# Wobblebot_Teensy_reroutPWR.net
KiCad netlist of a schematic drawn in EAGLE
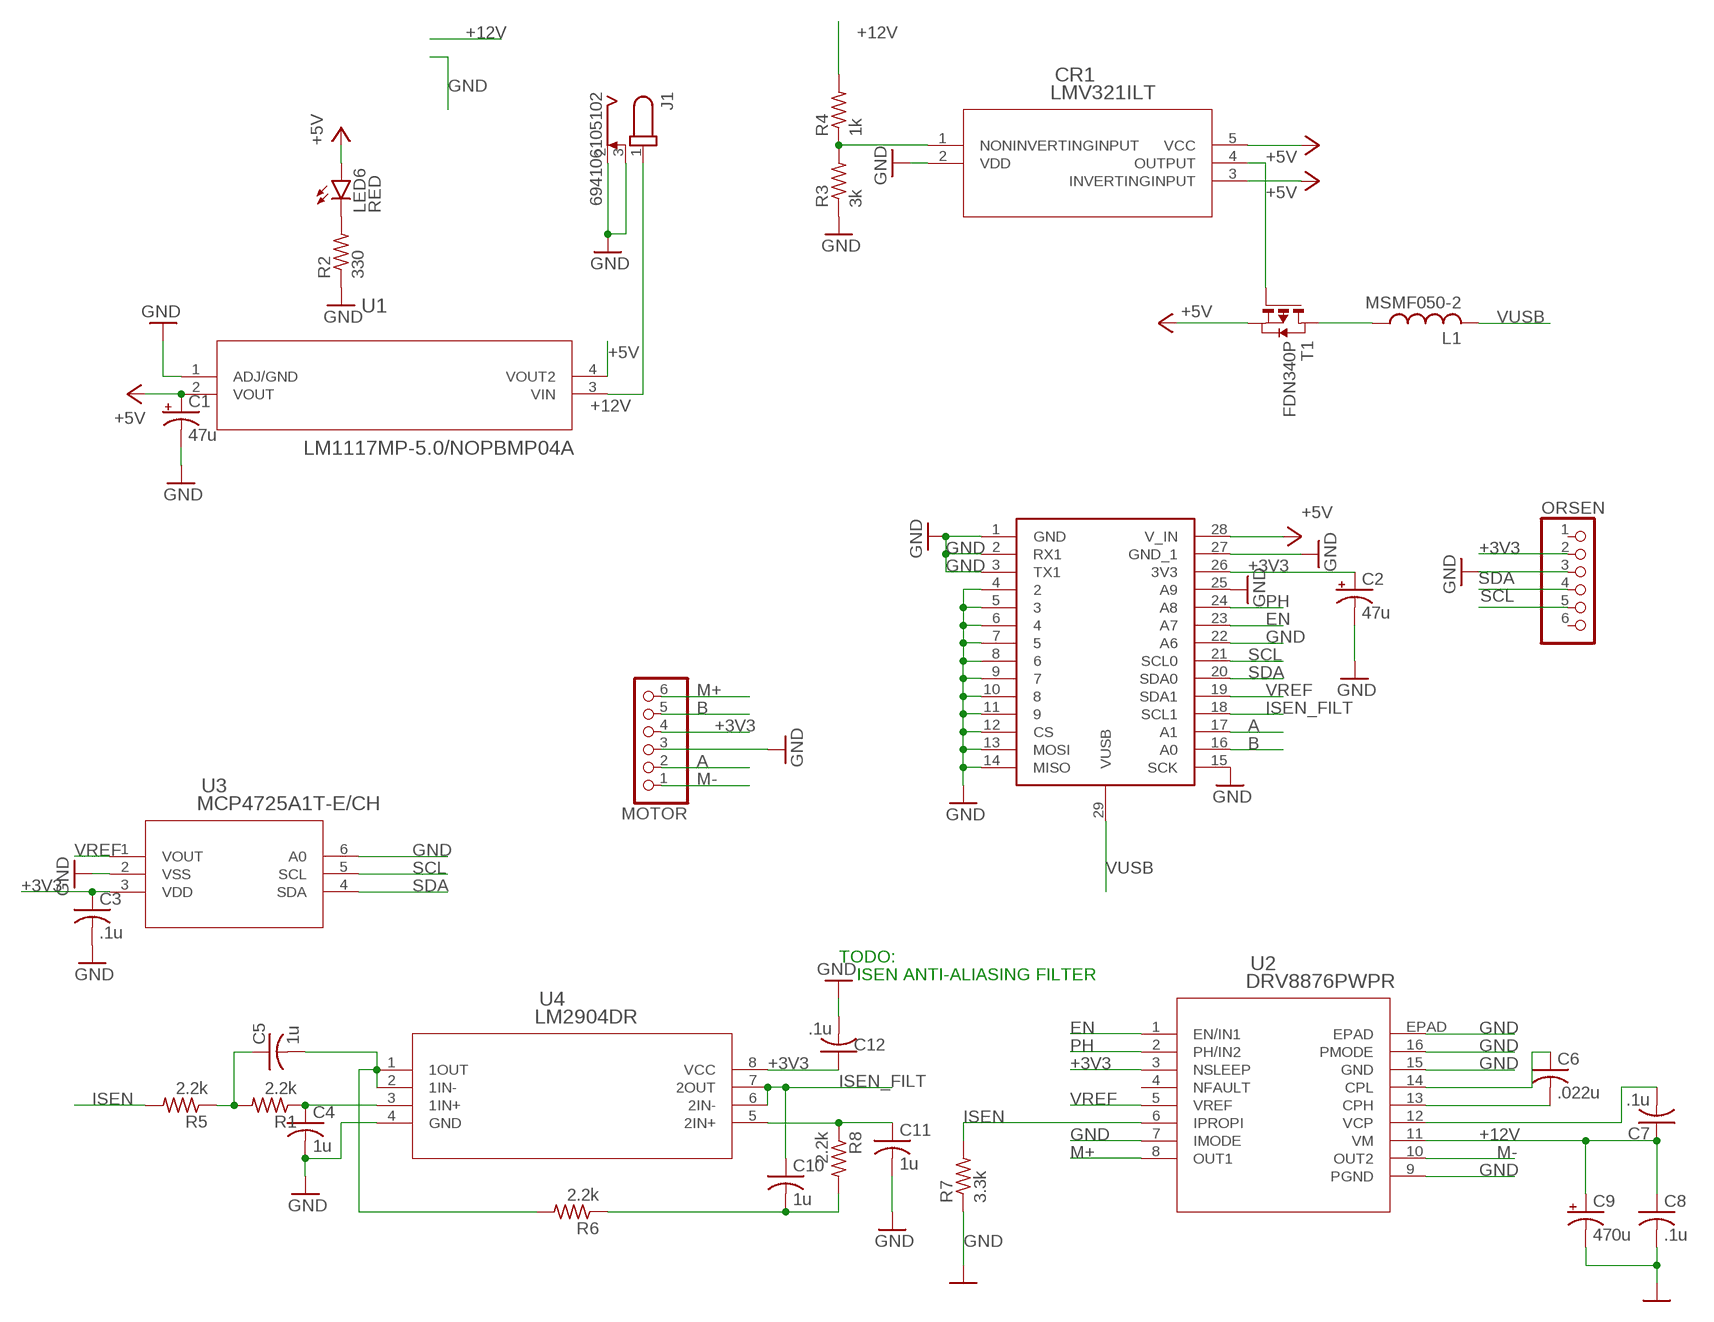
[diagram p0: schematic, sheet 1]

(export (version "E")
  (design (tool "Eeschema 10.0.6"))
  (components
    (comp (ref "C1")
      (value "47u")
      (footprint "eagle-import:153CLV-0605")
      (libsource (lib "eagle-import") (part "CPOL-US153CLV-0605"))
    )
    (comp (ref "C2")
      (value "47u")
      (footprint "eagle-import:153CLV-0605")
      (libsource (lib "eagle-import") (part "CPOL-US153CLV-0605"))
    )
    (comp (ref "C3")
      (value ".1u")
      (footprint "eagle-import:C0805")
      (libsource (lib "eagle-import") (part "C-USC0805"))
    )
    (comp (ref "C4")
      (value "1u")
      (footprint "eagle-import:C0805")
      (libsource (lib "eagle-import") (part "C-USC0805"))
    )
    (comp (ref "C5")
      (value "1u")
      (footprint "eagle-import:C0805")
      (libsource (lib "eagle-import") (part "C-USC0805"))
    )
    (comp (ref "C6")
      (value ".022u")
      (footprint "eagle-import:C0805")
      (libsource (lib "eagle-import") (part "C-USC0805"))
    )
    (comp (ref "C7")
      (value ".1u")
      (footprint "eagle-import:C0805")
      (libsource (lib "eagle-import") (part "C-USC0805"))
    )
    (comp (ref "C8")
      (value ".1u")
      (footprint "eagle-import:C0805")
      (libsource (lib "eagle-import") (part "C-USC0805"))
    )
    (comp (ref "C9")
      (value "470u")
      (footprint "eagle-import:E5-10,5")
      (libsource (lib "eagle-import") (part "CPOL-USE5-10.5"))
    )
    (comp (ref "C10")
      (value "1u")
      (footprint "eagle-import:C0805")
      (libsource (lib "eagle-import") (part "C-USC0805"))
    )
    (comp (ref "C11")
      (value "1u")
      (footprint "eagle-import:C0805")
      (libsource (lib "eagle-import") (part "C-USC0805"))
    )
    (comp (ref "C12")
      (value ".1u")
      (footprint "eagle-import:C0805")
      (libsource (lib "eagle-import") (part "C-USC0805"))
    )
    (comp (ref "CR1")
      (value "LMV321ILT")
      (footprint "eagle-import:SOT23-5")
      (libsource (lib "eagle-import") (part "LMV321ILT"))
    )
    (comp (ref "J1")
      (value "694106105102")
      (footprint "eagle-import:694106105102")
      (fields
        (field (name "DIGIKEY_PART_NUMBER") "732-5928-2-ND")
        (field (name "MANUFACTURER") "Wurth Electronics Inc.")
        (field (name "CREATED_BY") "PCBLayout.com")
      )
      (libsource (lib "eagle-import") (part "694106105102"))
    )
    (comp (ref "L1")
      (value "MSMF050-2")
      (footprint "eagle-import:L1812")
      (libsource (lib "eagle-import") (part "L-USL1812"))
    )
    (comp (ref "LED6")
      (value "RED")
      (footprint "eagle-import:CHIPLED_0805")
      (libsource (lib "eagle-import") (part "LEDCHIPLED_0805"))
    )
    (comp (ref "MOTOR")
      (value "PINHD-1X6")
      (footprint "eagle-import:1X06")
      (libsource (lib "eagle-import") (part "PINHD-1X6"))
    )
    (comp (ref "ORSEN")
      (value "PINHD-1X6")
      (footprint "eagle-import:1X06")
      (libsource (lib "eagle-import") (part "PINHD-1X6"))
    )
    (comp (ref "R1")
      (value "2.2k")
      (footprint "eagle-import:R0805")
      (libsource (lib "eagle-import") (part "R-US_R0805"))
    )
    (comp (ref "R2")
      (value "330")
      (footprint "eagle-import:R0805")
      (libsource (lib "eagle-import") (part "R-US_R0805"))
    )
    (comp (ref "R3")
      (value "3k")
      (footprint "eagle-import:R0805")
      (libsource (lib "eagle-import") (part "R-US_R0805"))
    )
    (comp (ref "R4")
      (value "1k")
      (footprint "eagle-import:R0805")
      (libsource (lib "eagle-import") (part "R-US_R0805"))
    )
    (comp (ref "R5")
      (value "2.2k")
      (footprint "eagle-import:R0805")
      (libsource (lib "eagle-import") (part "R-US_R0805"))
    )
    (comp (ref "R6")
      (value "2.2k")
      (footprint "eagle-import:R0805")
      (libsource (lib "eagle-import") (part "R-US_R0805"))
    )
    (comp (ref "R7")
      (value "3.3k")
      (footprint "eagle-import:R0805")
      (libsource (lib "eagle-import") (part "R-US_R0805"))
    )
    (comp (ref "R8")
      (value "2.2k")
      (footprint "eagle-import:R0805")
      (libsource (lib "eagle-import") (part "R-US_R0805"))
    )
    (comp (ref "T1")
      (value "FDN340P")
      (footprint "eagle-import:SOT-23")
      (libsource (lib "eagle-import") (part "PMOSSOT23"))
    )
    (comp (ref "U$1")
      (value "TEENSY4.0TEENSY4.0")
      (footprint "eagle-import:DIP1524W53P254L3810H508Q28B")
      (libsource (lib "eagle-import") (part "TEENSY4.0TEENSY4.0"))
    )
    (comp (ref "U1")
      (value "LM1117MP-5.0/NOPBMP04A")
      (footprint "eagle-import:MP04A")
      (fields (field (name "MANUFACTURER_PART_NUMBER") "LM1117MP5.0NOPB"))
      (libsource (lib "eagle-import") (part "LM1117MP-5.0/NOPBMP04A"))
    )
    (comp (ref "U2")
      (value "DRV8876PWPR")
      (footprint "eagle-import:PWP16_2P31X2P46")
      (fields (field (name "COPYRIGHT") "Copyright (C) 2018 Accelerated Designs. All rights reserved"))
      (libsource (lib "eagle-import") (part "DRV8876PWPR"))
    )
    (comp (ref "U3")
      (value "MCP4725A1T-E/CH")
      (footprint "eagle-import:SOT-23-6_MC")
      (fields (field (name "COPYRIGHT") "Copyright (C) 2018 Accelerated Designs. All rights reserved"))
      (libsource (lib "eagle-import") (part "MCP4725A1T-E/CH"))
    )
    (comp (ref "U4")
      (value "LM2904DR")
      (footprint "eagle-import:D8")
      (libsource (lib "eagle-import") (part "LM2904DR"))
    )
  )
  (nets
    (net (code "1") (name "+5V") (class "Default")
      (node (ref "C1") (pin "+") (pinfunction "+_+") (pintype "passive"))
      (node (ref "CR1") (pin "3") (pinfunction "INVERTINGINPUT_3") (pintype "input"))
      (node (ref "CR1") (pin "5") (pinfunction "VCC_5") (pintype "power_in"))
      (node (ref "LED6") (pin "A") (pinfunction "A_A") (pintype "passive"))
      (node (ref "T1") (pin "2") (pinfunction "S_2") (pintype "passive"))
      (node (ref "U$1") (pin "28") (pinfunction "V_IN_28") (pintype "bidirectional"))
      (node (ref "U1") (pin "2") (pinfunction "VOUT_2") (pintype "output"))
      (node (ref "U1") (pin "4") (pinfunction "VOUT2_4") (pintype "power_in"))
    )
    (net (code "2") (name "/+3V3") (class "Default")
      (node (ref "C12") (pin "1") (pinfunction "1_1") (pintype "passive"))
      (node (ref "C2") (pin "+") (pinfunction "+_+") (pintype "passive"))
      (node (ref "C3") (pin "1") (pinfunction "1_1") (pintype "passive"))
      (node (ref "MOTOR") (pin "4") (pinfunction "4_4") (pintype "passive"))
      (node (ref "ORSEN") (pin "2") (pinfunction "2_2") (pintype "passive"))
      (node (ref "U$1") (pin "26") (pinfunction "3V3_26") (pintype "bidirectional"))
      (node (ref "U2") (pin "3") (pinfunction "NSLEEP_3") (pintype "passive"))
      (node (ref "U3") (pin "3") (pinfunction "VDD_3") (pintype "passive"))
      (node (ref "U4") (pin "8") (pinfunction "VCC_8") (pintype "power_in"))
    )
    (net (code "3") (name "/+12V") (class "Default")
      (node (ref "C7") (pin "1") (pinfunction "1_1") (pintype "passive"))
      (node (ref "C8") (pin "1") (pinfunction "1_1") (pintype "passive"))
      (node (ref "C9") (pin "+") (pinfunction "+_+") (pintype "passive"))
      (node (ref "J1") (pin "1") (pinfunction "1_1") (pintype "passive"))
      (node (ref "R4") (pin "2") (pinfunction "2_2") (pintype "passive"))
      (node (ref "U1") (pin "3") (pinfunction "VIN_3") (pintype "input"))
      (node (ref "U2") (pin "11") (pinfunction "VM_11") (pintype "passive"))
    )
    (net (code "4") (name "/A") (class "Default")
      (node (ref "MOTOR") (pin "2") (pinfunction "2_2") (pintype "passive"))
      (node (ref "U$1") (pin "17") (pinfunction "A1_17") (pintype "bidirectional"))
    )
    (net (code "5") (name "/B") (class "Default")
      (node (ref "MOTOR") (pin "5") (pinfunction "5_5") (pintype "passive"))
      (node (ref "U$1") (pin "16") (pinfunction "A0_16") (pintype "bidirectional"))
    )
    (net (code "6") (name "/EN") (class "Default")
      (node (ref "U$1") (pin "23") (pinfunction "A7_23") (pintype "bidirectional"))
      (node (ref "U2") (pin "1") (pinfunction "EN/IN1_1") (pintype "input"))
    )
    (net (code "7") (name "/ISEN") (class "Default")
      (node (ref "R5") (pin "2") (pinfunction "2_2") (pintype "passive"))
      (node (ref "R7") (pin "2") (pinfunction "2_2") (pintype "passive"))
      (node (ref "U2") (pin "6") (pinfunction "IPROPI_6") (pintype "passive"))
    )
    (net (code "8") (name "/ISEN_FILT") (class "Default")
      (node (ref "C10") (pin "1") (pinfunction "1_1") (pintype "passive"))
      (node (ref "U$1") (pin "18") (pinfunction "SCL1_18") (pintype "bidirectional"))
      (node (ref "U4") (pin "6") (pinfunction "2IN-_6") (pintype "input"))
      (node (ref "U4") (pin "7") (pinfunction "2OUT_7") (pintype "output"))
    )
    (net (code "9") (name "/M+") (class "Default")
      (node (ref "MOTOR") (pin "6") (pinfunction "6_6") (pintype "passive"))
      (node (ref "U2") (pin "8") (pinfunction "OUT1_8") (pintype "output"))
    )
    (net (code "10") (name "/M-") (class "Default")
      (node (ref "MOTOR") (pin "1") (pinfunction "1_1") (pintype "passive"))
      (node (ref "U2") (pin "10") (pinfunction "OUT2_10") (pintype "output"))
    )
    (net (code "11") (name "/PH") (class "Default")
      (node (ref "U$1") (pin "24") (pinfunction "A8_24") (pintype "bidirectional"))
      (node (ref "U2") (pin "2") (pinfunction "PH/IN2_2") (pintype "input"))
    )
    (net (code "12") (name "/SCL") (class "Default")
      (node (ref "ORSEN") (pin "5") (pinfunction "5_5") (pintype "passive"))
      (node (ref "U$1") (pin "21") (pinfunction "SCL0_21") (pintype "bidirectional"))
      (node (ref "U3") (pin "5") (pinfunction "SCL_5") (pintype "passive"))
    )
    (net (code "13") (name "/SDA") (class "Default")
      (node (ref "ORSEN") (pin "4") (pinfunction "4_4") (pintype "passive"))
      (node (ref "U$1") (pin "20") (pinfunction "SDA0_20") (pintype "bidirectional"))
      (node (ref "U3") (pin "4") (pinfunction "SDA_4") (pintype "passive"))
    )
    (net (code "14") (name "/VREF") (class "Default")
      (node (ref "U$1") (pin "19") (pinfunction "SDA1_19") (pintype "bidirectional"))
      (node (ref "U2") (pin "5") (pinfunction "VREF_5") (pintype "power_in"))
      (node (ref "U3") (pin "1") (pinfunction "VOUT_1") (pintype "passive"))
    )
    (net (code "15") (name "/VUSB") (class "Default")
      (node (ref "L1") (pin "2") (pinfunction "2_2") (pintype "passive"))
      (node (ref "U$1") (pin "29") (pinfunction "VUSB_29") (pintype "bidirectional"))
    )
    (net (code "16") (name "GND") (class "Default")
      (node (ref "C1") (pin "-") (pinfunction "-_-") (pintype "passive"))
      (node (ref "C11") (pin "2") (pinfunction "2_2") (pintype "passive"))
      (node (ref "C12") (pin "2") (pinfunction "2_2") (pintype "passive"))
      (node (ref "C2") (pin "-") (pinfunction "-_-") (pintype "passive"))
      (node (ref "C3") (pin "2") (pinfunction "2_2") (pintype "passive"))
      (node (ref "C4") (pin "2") (pinfunction "2_2") (pintype "passive"))
      (node (ref "C8") (pin "2") (pinfunction "2_2") (pintype "passive"))
      (node (ref "C9") (pin "-") (pinfunction "-_-") (pintype "passive"))
      (node (ref "CR1") (pin "2") (pinfunction "VDD_2") (pintype "power_in"))
      (node (ref "J1") (pin "2") (pinfunction "2_2") (pintype "passive"))
      (node (ref "J1") (pin "3") (pinfunction "3_3") (pintype "passive"))
      (node (ref "MOTOR") (pin "3") (pinfunction "3_3") (pintype "passive"))
      (node (ref "ORSEN") (pin "3") (pinfunction "3_3") (pintype "passive"))
      (node (ref "R2") (pin "1") (pinfunction "1_1") (pintype "passive"))
      (node (ref "R3") (pin "1") (pinfunction "1_1") (pintype "passive"))
      (node (ref "R7") (pin "1") (pinfunction "1_1") (pintype "passive"))
      (node (ref "U$1") (pin "1") (pinfunction "GND_1") (pintype "bidirectional"))
      (node (ref "U$1") (pin "10") (pinfunction "8_10") (pintype "bidirectional"))
      (node (ref "U$1") (pin "11") (pinfunction "9_11") (pintype "bidirectional"))
      (node (ref "U$1") (pin "12") (pinfunction "CS_12") (pintype "bidirectional"))
      (node (ref "U$1") (pin "13") (pinfunction "MOSI_13") (pintype "bidirectional"))
      (node (ref "U$1") (pin "14") (pinfunction "MISO_14") (pintype "bidirectional"))
      (node (ref "U$1") (pin "15") (pinfunction "SCK_15") (pintype "bidirectional"))
      (node (ref "U$1") (pin "2") (pinfunction "RX1_2") (pintype "bidirectional"))
      (node (ref "U$1") (pin "22") (pinfunction "A6_22") (pintype "bidirectional"))
      (node (ref "U$1") (pin "25") (pinfunction "A9_25") (pintype "bidirectional"))
      (node (ref "U$1") (pin "27") (pinfunction "GND_1_27") (pintype "bidirectional"))
      (node (ref "U$1") (pin "3") (pinfunction "TX1_3") (pintype "bidirectional"))
      (node (ref "U$1") (pin "4") (pinfunction "2_4") (pintype "bidirectional"))
      (node (ref "U$1") (pin "5") (pinfunction "3_5") (pintype "bidirectional"))
      (node (ref "U$1") (pin "6") (pinfunction "4_6") (pintype "bidirectional"))
      (node (ref "U$1") (pin "7") (pinfunction "5_7") (pintype "bidirectional"))
      (node (ref "U$1") (pin "8") (pinfunction "6_8") (pintype "bidirectional"))
      (node (ref "U$1") (pin "9") (pinfunction "7_9") (pintype "bidirectional"))
      (node (ref "U1") (pin "1") (pinfunction "ADJ/GND_1") (pintype "passive"))
      (node (ref "U2") (pin "15") (pinfunction "GND_15") (pintype "passive"))
      (node (ref "U2") (pin "16") (pinfunction "PMODE_16") (pintype "passive"))
      (node (ref "U2") (pin "7") (pinfunction "IMODE_7") (pintype "passive"))
      (node (ref "U2") (pin "9") (pinfunction "PGND_9") (pintype "passive"))
      (node (ref "U2") (pin "EPAD") (pinfunction "EPAD_EPAD") (pintype "passive"))
      (node (ref "U3") (pin "2") (pinfunction "VSS_2") (pintype "passive"))
      (node (ref "U3") (pin "6") (pinfunction "A0_6") (pintype "passive"))
      (node (ref "U4") (pin "4") (pinfunction "GND_4") (pintype "power_in"))
    )
    (net (code "17") (name "Net-(C5-Pad1)") (class "Default")
      (node (ref "C5") (pin "1") (pinfunction "1_1") (pintype "passive"))
      (node (ref "R1") (pin "2") (pinfunction "2_2") (pintype "passive"))
      (node (ref "R5") (pin "1") (pinfunction "1_1") (pintype "passive"))
    )
    (net (code "18") (name "Net-(C10-Pad2)") (class "Default")
      (node (ref "C10") (pin "2") (pinfunction "2_2") (pintype "passive"))
      (node (ref "R6") (pin "1") (pinfunction "1_1") (pintype "passive"))
      (node (ref "R8") (pin "2") (pinfunction "2_2") (pintype "passive"))
    )
    (net (code "19") (name "Net-(CR1-NONINVERTINGINPUT)") (class "Default")
      (node (ref "CR1") (pin "1") (pinfunction "NONINVERTINGINPUT_1") (pintype "input"))
      (node (ref "R3") (pin "2") (pinfunction "2_2") (pintype "passive"))
      (node (ref "R4") (pin "1") (pinfunction "1_1") (pintype "passive"))
    )
    (net (code "20") (name "Net-(CR1-OUTPUT)") (class "Default")
      (node (ref "CR1") (pin "4") (pinfunction "OUTPUT_4") (pintype "output"))
      (node (ref "T1") (pin "3") (pinfunction "G_3") (pintype "passive"))
    )
    (net (code "21") (name "Net-(LED6-PadC)") (class "Default")
      (node (ref "LED6") (pin "C") (pinfunction "C_C") (pintype "passive"))
      (node (ref "R2") (pin "2") (pinfunction "2_2") (pintype "passive"))
    )
    (net (code "22") (name "Net-(T1-D)") (class "Default")
      (node (ref "L1") (pin "1") (pinfunction "1_1") (pintype "passive"))
      (node (ref "T1") (pin "1") (pinfunction "D_1") (pintype "passive"))
    )
    (net (code "23") (name "Net-(U2-CPH)") (class "Default")
      (node (ref "C6") (pin "2") (pinfunction "2_2") (pintype "passive"))
      (node (ref "U2") (pin "13") (pinfunction "CPH_13") (pintype "passive"))
    )
    (net (code "24") (name "Net-(U2-CPL)") (class "Default")
      (node (ref "C6") (pin "1") (pinfunction "1_1") (pintype "passive"))
      (node (ref "U2") (pin "14") (pinfunction "CPL_14") (pintype "passive"))
    )
    (net (code "25") (name "Net-(U2-VCP)") (class "Default")
      (node (ref "C7") (pin "2") (pinfunction "2_2") (pintype "passive"))
      (node (ref "U2") (pin "12") (pinfunction "VCP_12") (pintype "passive"))
    )
    (net (code "26") (name "Net-(U4-1IN+)") (class "Default")
      (node (ref "C4") (pin "1") (pinfunction "1_1") (pintype "passive"))
      (node (ref "R1") (pin "1") (pinfunction "1_1") (pintype "passive"))
      (node (ref "U4") (pin "3") (pinfunction "1IN+_3") (pintype "input"))
    )
    (net (code "27") (name "Net-(U4-1IN-)") (class "Default")
      (node (ref "C5") (pin "2") (pinfunction "2_2") (pintype "passive"))
      (node (ref "R6") (pin "2") (pinfunction "2_2") (pintype "passive"))
      (node (ref "U4") (pin "1") (pinfunction "1OUT_1") (pintype "output"))
      (node (ref "U4") (pin "2") (pinfunction "1IN-_2") (pintype "input"))
    )
    (net (code "28") (name "Net-(U4-2IN+)") (class "Default")
      (node (ref "C11") (pin "1") (pinfunction "1_1") (pintype "passive"))
      (node (ref "R8") (pin "1") (pinfunction "1_1") (pintype "passive"))
      (node (ref "U4") (pin "5") (pinfunction "2IN+_5") (pintype "input"))
    )
    (net (code "29") (name "unconnected-(ORSEN-Pad1)") (class "Default")
      (node (ref "ORSEN") (pin "1") (pinfunction "1_1") (pintype "passive"))
    )
    (net (code "30") (name "unconnected-(ORSEN-Pad6)") (class "Default")
      (node (ref "ORSEN") (pin "6") (pinfunction "6_6") (pintype "passive"))
    )
    (net (code "31") (name "unconnected-(U2-NFAULT-Pad4)") (class "Default")
      (node (ref "U2") (pin "4") (pinfunction "NFAULT_4") (pintype "passive"))
    )
  )
)
